# Color_Light_Sensor_Board.net
KiCad netlist of a schematic drawn in EAGLE
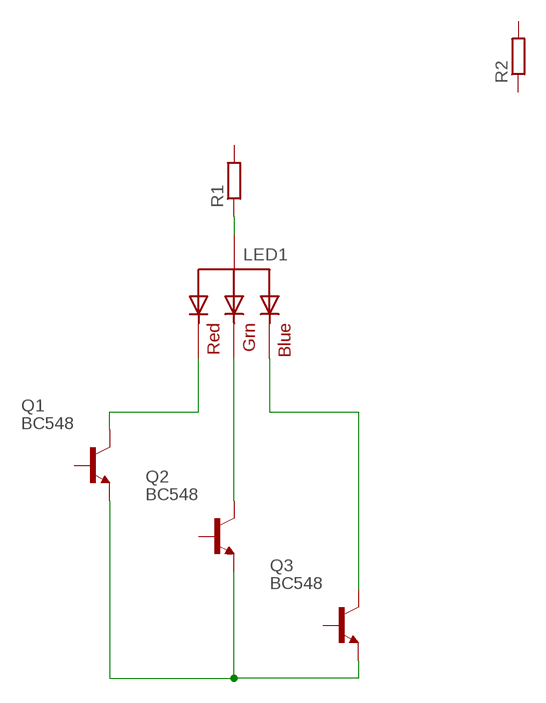
[diagram p0: schematic, sheet 1]

(export (version "E")
  (design (tool "Eeschema 10.0.6"))
  (components
    (comp (ref "LED1")
      (value "RGBLED_CA-5MM")
      (footprint "eagle-import:LED5MMRGB")
      (libsource (lib "eagle-import") (part "RGBLED_CA-5MM"))
    )
    (comp (ref "Q1")
      (value "BC548")
      (footprint "eagle-import:TO92-EBC")
      (libsource (lib "eagle-import") (part "BC548"))
    )
    (comp (ref "Q2")
      (value "BC548")
      (footprint "eagle-import:TO92-EBC")
      (libsource (lib "eagle-import") (part "BC548"))
    )
    (comp (ref "Q3")
      (value "BC548")
      (footprint "eagle-import:TO92-EBC")
      (libsource (lib "eagle-import") (part "BC548"))
    )
    (comp (ref "R1")
      (value "R-EU_0204/7")
      (footprint "eagle-import:0204_7")
      (libsource (lib "eagle-import") (part "R-EU_0204/7"))
    )
    (comp (ref "R2")
      (value "R-EU_0204/2V")
      (footprint "eagle-import:0204V")
      (libsource (lib "eagle-import") (part "resistor_R-EU_0204/2V"))
    )
  )
  (nets
    (net (code "1") (name "Net-(LED1-BLUE)") (class "Default")
      (node (ref "LED1") (pin "4") (pinfunction "BLUE_4") (pintype "bidirectional"))
      (node (ref "Q3") (pin "C") (pinfunction "C_C") (pintype "passive"))
    )
    (net (code "2") (name "Net-(LED1-GREEN)") (class "Default")
      (node (ref "LED1") (pin "3") (pinfunction "GREEN_3") (pintype "bidirectional"))
      (node (ref "Q2") (pin "C") (pinfunction "C_C") (pintype "passive"))
    )
    (net (code "3") (name "Net-(LED1-RED)") (class "Default")
      (node (ref "LED1") (pin "1") (pinfunction "RED_1") (pintype "bidirectional"))
      (node (ref "Q1") (pin "C") (pinfunction "C_C") (pintype "passive"))
    )
    (net (code "4") (name "Net-(LED1-VCC)") (class "Default")
      (node (ref "LED1") (pin "2") (pinfunction "VCC_2") (pintype "bidirectional"))
      (node (ref "R1") (pin "1") (pinfunction "1_1") (pintype "passive"))
    )
    (net (code "5") (name "Net-(Q1-PadE)") (class "Default")
      (node (ref "Q1") (pin "E") (pinfunction "E_E") (pintype "passive"))
      (node (ref "Q2") (pin "E") (pinfunction "E_E") (pintype "passive"))
      (node (ref "Q3") (pin "E") (pinfunction "E_E") (pintype "passive"))
    )
    (net (code "6") (name "unconnected-(Q1-PadB)") (class "Default")
      (node (ref "Q1") (pin "B") (pinfunction "B_B") (pintype "passive"))
    )
    (net (code "7") (name "unconnected-(Q2-PadB)") (class "Default")
      (node (ref "Q2") (pin "B") (pinfunction "B_B") (pintype "passive"))
    )
    (net (code "8") (name "unconnected-(Q3-PadB)") (class "Default")
      (node (ref "Q3") (pin "B") (pinfunction "B_B") (pintype "passive"))
    )
    (net (code "9") (name "unconnected-(R1-Pad2)") (class "Default")
      (node (ref "R1") (pin "2") (pinfunction "2_2") (pintype "passive"))
    )
    (net (code "10") (name "unconnected-(R2-Pad1)") (class "Default")
      (node (ref "R2") (pin "1") (pinfunction "1_1") (pintype "passive"))
    )
    (net (code "11") (name "unconnected-(R2-Pad2)") (class "Default")
      (node (ref "R2") (pin "2") (pinfunction "2_2") (pintype "passive"))
    )
  )
)
